# ESP32_Easyeda_schematic.net
KiCad netlist of a schematic drawn in EasyEDA
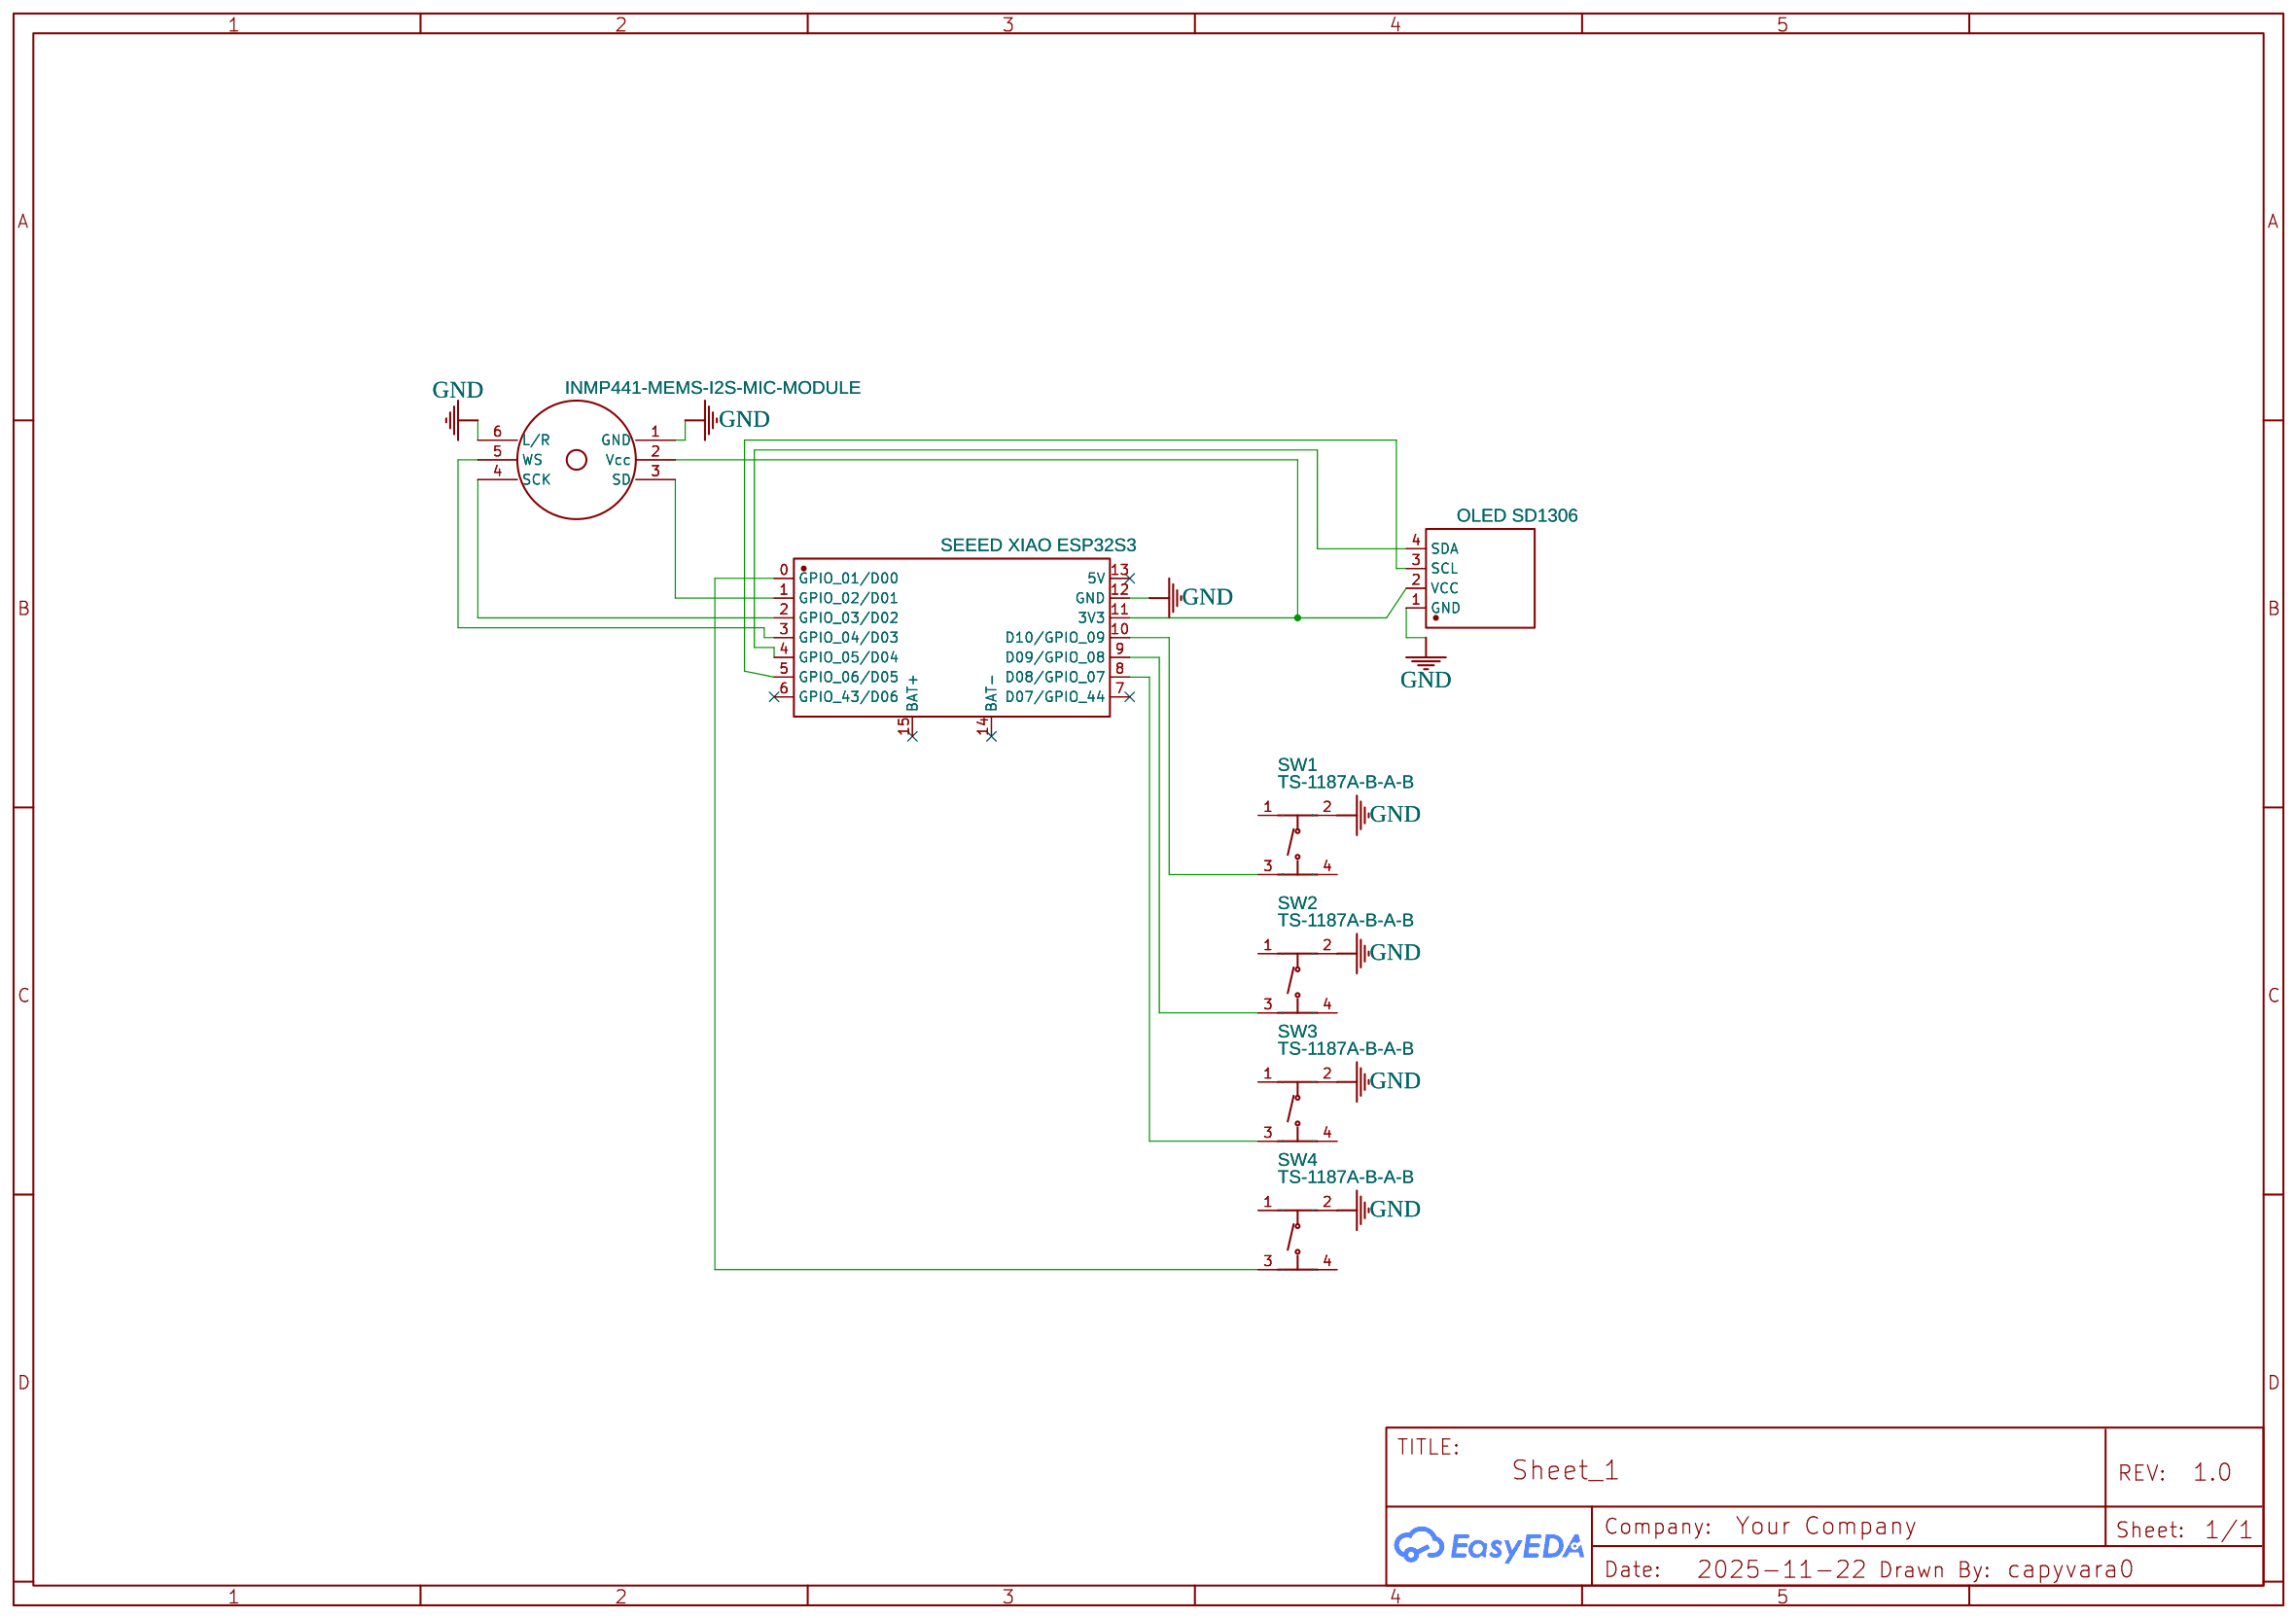
[diagram p0: schematic sheet]

(export (version "E")
  (design (tool "Eeschema 10.0.6"))
  (components
    (comp (ref "SW1")
      (value "TS-1187A-B-A-B")
      (fields (field (name "Manufacturer") "XKB Connection(中国星坤)"))
      (libsource (lib "") (part "TS-1187A-B-A-B"))
    )
    (comp (ref "SW2")
      (value "TS-1187A-B-A-B")
      (fields (field (name "Manufacturer") "XKB Connection(中国星坤)"))
      (libsource (lib "") (part "TS-1187A-B-A-B"))
    )
    (comp (ref "SW3")
      (value "TS-1187A-B-A-B")
      (fields (field (name "Manufacturer") "XKB Connection(中国星坤)"))
      (libsource (lib "") (part "TS-1187A-B-A-B"))
    )
    (comp (ref "SW4")
      (value "TS-1187A-B-A-B")
      (fields (field (name "Manufacturer") "XKB Connection(中国星坤)"))
      (libsource (lib "") (part "TS-1187A-B-A-B"))
    )
    (comp (ref "U1")
      (value "SEEED XIAO ESP32S3")
      (fields (field (name "Manufacturer Part") "Xiao") (field (name "Manufacturer") "Seeeduino"))
      (libsource (lib "") (part "SEEED XIAO ESP32S3"))
    )
    (comp (ref "U2")
      (value "INMP441-MEMS-I2S-MIC-MODULE")
      (libsource (lib "") (part "INMP441-MEMS-I2S-MIC-MODULE"))
    )
    (comp (ref "U4")
      (value "OLED SD1306")
      (fields (field (name "Manufacturer Part") "1.3寸OLED显示屏12864"))
      (libsource (lib "") (part "OLED SD1306"))
    )
  )
  (nets
    (net (code "1") (name "GND") (class "Default")
      (node (ref "SW1") (pin "2") (pinfunction "B_2") (pintype "unspecified"))
      (node (ref "SW2") (pin "2") (pinfunction "B_2") (pintype "unspecified"))
      (node (ref "SW3") (pin "2") (pinfunction "B_2") (pintype "unspecified"))
      (node (ref "SW4") (pin "2") (pinfunction "B_2") (pintype "unspecified"))
      (node (ref "U1") (pin "12") (pinfunction "GND_12") (pintype "unspecified"))
      (node (ref "U2") (pin "1") (pinfunction "GND_1") (pintype "unspecified"))
      (node (ref "U2") (pin "6") (pinfunction "L/R_6") (pintype "unspecified"))
      (node (ref "U4") (pin "1") (pinfunction "GND_1") (pintype "unspecified"))
    )
    (net (code "2") (name "Net-(SW1-C)") (class "Default")
      (node (ref "SW1") (pin "3") (pinfunction "C_3") (pintype "unspecified"))
      (node (ref "U1") (pin "10") (pinfunction "D10/GPIO_09_10") (pintype "unspecified"))
    )
    (net (code "3") (name "Net-(SW2-C)") (class "Default")
      (node (ref "SW2") (pin "3") (pinfunction "C_3") (pintype "unspecified"))
      (node (ref "U1") (pin "9") (pinfunction "D09/GPIO_08_9") (pintype "unspecified"))
    )
    (net (code "4") (name "Net-(SW3-C)") (class "Default")
      (node (ref "SW3") (pin "3") (pinfunction "C_3") (pintype "unspecified"))
      (node (ref "U1") (pin "8") (pinfunction "D08/GPIO_07_8") (pintype "unspecified"))
    )
    (net (code "5") (name "Net-(SW4-C)") (class "Default")
      (node (ref "SW4") (pin "3") (pinfunction "C_3") (pintype "unspecified"))
      (node (ref "U1") (pin "0") (pinfunction "GPIO_01/D00_0") (pintype "unspecified"))
    )
    (net (code "6") (name "Net-(U1-3V3)") (class "Default")
      (node (ref "U1") (pin "11") (pinfunction "3V3_11") (pintype "unspecified"))
      (node (ref "U2") (pin "2") (pinfunction "Vcc_2") (pintype "unspecified"))
      (node (ref "U4") (pin "2") (pinfunction "VCC_2") (pintype "unspecified"))
    )
    (net (code "7") (name "Net-(U1-GPIO_02{slash}D01)") (class "Default")
      (node (ref "U1") (pin "1") (pinfunction "GPIO_02/D01_1") (pintype "unspecified"))
      (node (ref "U2") (pin "3") (pinfunction "SD_3") (pintype "unspecified"))
    )
    (net (code "8") (name "Net-(U1-GPIO_03{slash}D02)") (class "Default")
      (node (ref "U1") (pin "2") (pinfunction "GPIO_03/D02_2") (pintype "unspecified"))
      (node (ref "U2") (pin "4") (pinfunction "SCK_4") (pintype "unspecified"))
    )
    (net (code "9") (name "Net-(U1-GPIO_04{slash}D03)") (class "Default")
      (node (ref "U1") (pin "3") (pinfunction "GPIO_04/D03_3") (pintype "unspecified"))
      (node (ref "U2") (pin "5") (pinfunction "WS_5") (pintype "unspecified"))
    )
    (net (code "10") (name "Net-(U1-GPIO_05{slash}D04)") (class "Default")
      (node (ref "U1") (pin "4") (pinfunction "GPIO_05/D04_4") (pintype "unspecified"))
      (node (ref "U4") (pin "4") (pinfunction "SDA_4") (pintype "unspecified"))
    )
    (net (code "11") (name "Net-(U1-GPIO_06{slash}D05)") (class "Default")
      (node (ref "U1") (pin "5") (pinfunction "GPIO_06/D05_5") (pintype "unspecified"))
      (node (ref "U4") (pin "3") (pinfunction "SCL_3") (pintype "unspecified"))
    )
    (net (code "12") (name "unconnected-(SW1-A-Pad1)") (class "Default")
      (node (ref "SW1") (pin "1") (pinfunction "A_1") (pintype "unspecified"))
    )
    (net (code "13") (name "unconnected-(SW1-D-Pad4)") (class "Default")
      (node (ref "SW1") (pin "4") (pinfunction "D_4") (pintype "unspecified"))
    )
    (net (code "14") (name "unconnected-(SW2-A-Pad1)") (class "Default")
      (node (ref "SW2") (pin "1") (pinfunction "A_1") (pintype "unspecified"))
    )
    (net (code "15") (name "unconnected-(SW2-D-Pad4)") (class "Default")
      (node (ref "SW2") (pin "4") (pinfunction "D_4") (pintype "unspecified"))
    )
    (net (code "16") (name "unconnected-(SW3-A-Pad1)") (class "Default")
      (node (ref "SW3") (pin "1") (pinfunction "A_1") (pintype "unspecified"))
    )
    (net (code "17") (name "unconnected-(SW3-D-Pad4)") (class "Default")
      (node (ref "SW3") (pin "4") (pinfunction "D_4") (pintype "unspecified"))
    )
    (net (code "18") (name "unconnected-(SW4-A-Pad1)") (class "Default")
      (node (ref "SW4") (pin "1") (pinfunction "A_1") (pintype "unspecified"))
    )
    (net (code "19") (name "unconnected-(SW4-D-Pad4)") (class "Default")
      (node (ref "SW4") (pin "4") (pinfunction "D_4") (pintype "unspecified"))
    )
    (net (code "20") (name "unconnected-(U1-5V-Pad13)") (class "Default")
      (node (ref "U1") (pin "13") (pinfunction "5V_13") (pintype "unspecified+no_connect"))
    )
    (net (code "21") (name "unconnected-(U1-BAT+-Pad15)") (class "Default")
      (node (ref "U1") (pin "15") (pinfunction "BAT+_15") (pintype "unspecified+no_connect"))
    )
    (net (code "22") (name "unconnected-(U1-BAT--Pad14)") (class "Default")
      (node (ref "U1") (pin "14") (pinfunction "BAT-_14") (pintype "unspecified+no_connect"))
    )
    (net (code "23") (name "unconnected-(U1-D07{slash}GPIO_44-Pad7)") (class "Default")
      (node (ref "U1") (pin "7") (pinfunction "D07/GPIO_44_7") (pintype "unspecified+no_connect"))
    )
    (net (code "24") (name "unconnected-(U1-GPIO_43{slash}D06-Pad6)") (class "Default")
      (node (ref "U1") (pin "6") (pinfunction "GPIO_43/D06_6") (pintype "unspecified+no_connect"))
    )
  )
)
